# NodeLORA.net
KiCad netlist of a schematic drawn in Altium Designer
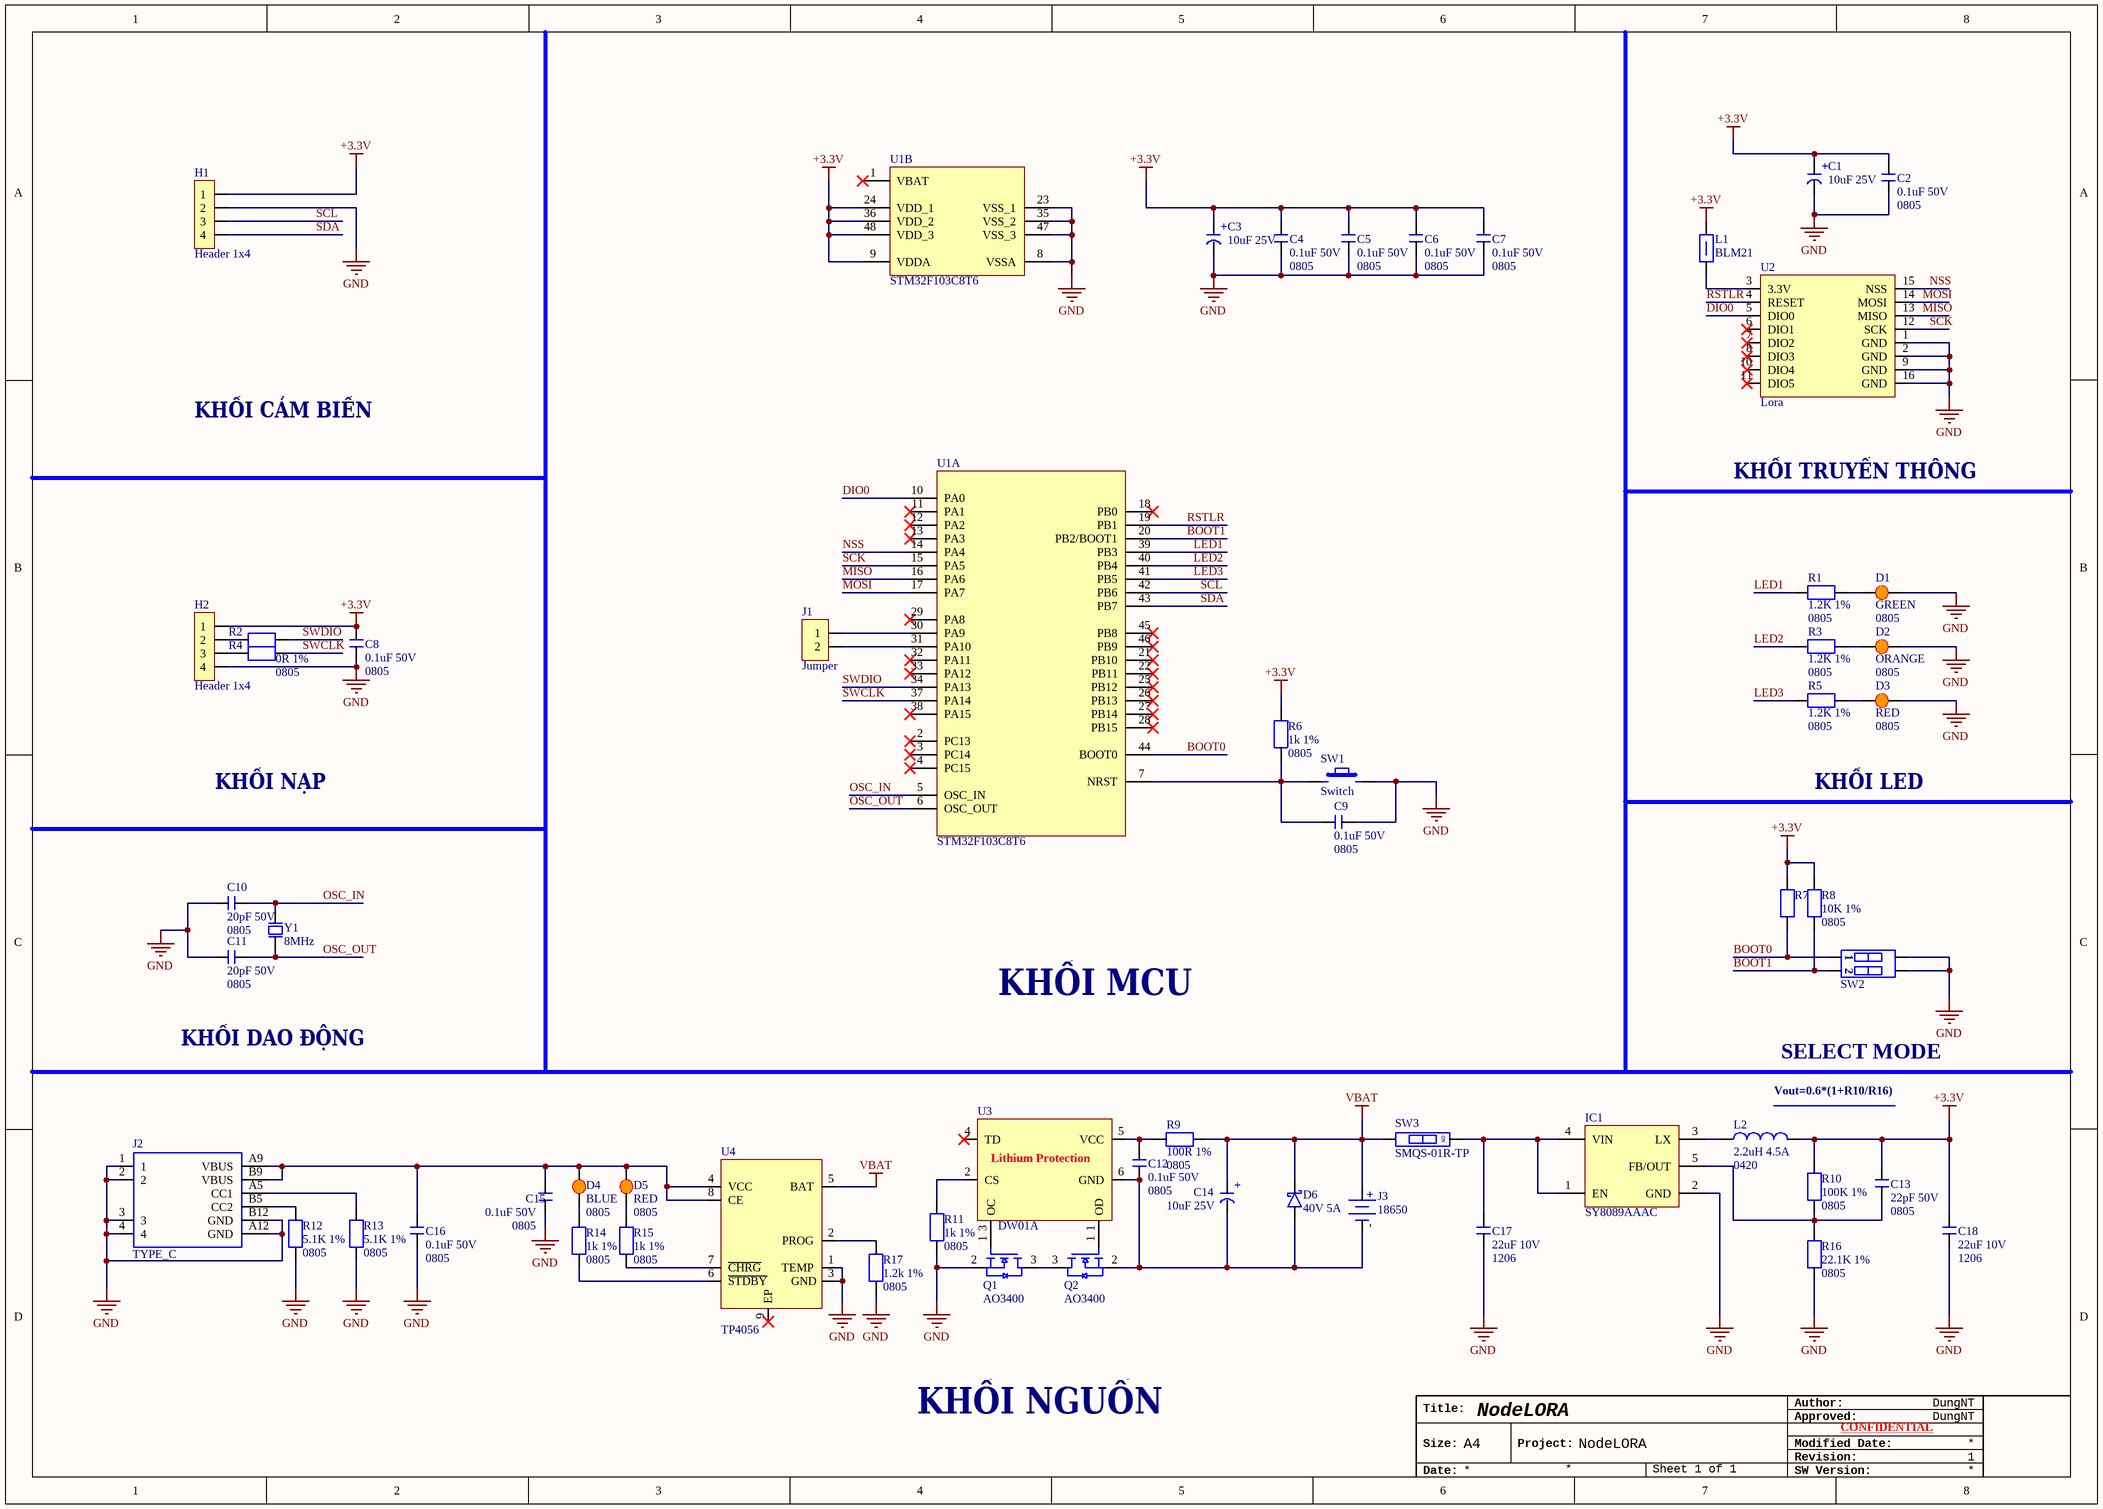
[diagram p0: NodeLORA.SchDoc]

(export (version "E")
  (design (tool "Eeschema 10.0.6"))
  (components
    (comp (ref "C1")
      (value "10uF 25V")
      (footprint "CAP-ALU-B")
      (description "10uF 25V 15mA@120Hz ±20% SMD,D4xL5.4mm Aluminum Electrolytic Capacitors - SMD ROHS")
      (fields (field (name "MANUFACTURER") "DMBJ"))
      (libsource (lib "Capacitor") (part "CAP_ALU_B_10uF_25V"))
    )
    (comp (ref "C2")
      (value "0.1uF 50V")
      (footprint "C0805")
      (description "0.1 µF ±10% 50V Ceramic Capacitor X7R 0805 (2012 Metric)")
      (fields (field (name "MANUFACTURER") "YAGEO") (field (name "PACKAGE") "0805"))
      (libsource (lib "Capacitor") (part "C0805_0.1uF_50V_10%"))
    )
    (comp (ref "C3")
      (value "10uF 25V")
      (footprint "CAP-ALU-B")
      (description "10uF 25V 15mA@120Hz ±20% SMD,D4xL5.4mm Aluminum Electrolytic Capacitors - SMD ROHS")
      (fields (field (name "MANUFACTURER") "DMBJ"))
      (libsource (lib "Capacitor") (part "CAP_ALU_B_10uF_25V"))
    )
    (comp (ref "C4")
      (value "0.1uF 50V")
      (footprint "C0805")
      (description "0.1 µF ±10% 50V Ceramic Capacitor X7R 0805 (2012 Metric)")
      (fields (field (name "MANUFACTURER") "YAGEO") (field (name "PACKAGE") "0805"))
      (libsource (lib "Capacitor") (part "C0805_0.1uF_50V_10%"))
    )
    (comp (ref "C5")
      (value "0.1uF 50V")
      (footprint "C0805")
      (description "0.1 µF ±10% 50V Ceramic Capacitor X7R 0805 (2012 Metric)")
      (fields (field (name "MANUFACTURER") "YAGEO") (field (name "PACKAGE") "0805"))
      (libsource (lib "Capacitor") (part "C0805_0.1uF_50V_10%"))
    )
    (comp (ref "C6")
      (value "0.1uF 50V")
      (footprint "C0805")
      (description "0.1 µF ±10% 50V Ceramic Capacitor X7R 0805 (2012 Metric)")
      (fields (field (name "MANUFACTURER") "YAGEO") (field (name "PACKAGE") "0805"))
      (libsource (lib "Capacitor") (part "C0805_0.1uF_50V_10%"))
    )
    (comp (ref "C7")
      (value "0.1uF 50V")
      (footprint "C0805")
      (description "0.1 µF ±10% 50V Ceramic Capacitor X7R 0805 (2012 Metric)")
      (fields (field (name "MANUFACTURER") "YAGEO") (field (name "PACKAGE") "0805"))
      (libsource (lib "Capacitor") (part "C0805_0.1uF_50V_10%"))
    )
    (comp (ref "C8")
      (value "0.1uF 50V")
      (footprint "C0805")
      (description "0.1 µF ±10% 50V Ceramic Capacitor X7R 0805 (2012 Metric)")
      (fields (field (name "MANUFACTURER") "YAGEO") (field (name "PACKAGE") "0805"))
      (libsource (lib "Capacitor") (part "C0805_0.1uF_50V_10%"))
    )
    (comp (ref "C9")
      (value "0.1uF 50V")
      (footprint "C0805")
      (description "0.1 µF ±10% 50V Ceramic Capacitor X7R 0805 (2012 Metric)")
      (fields (field (name "MANUFACTURER") "YAGEO") (field (name "PACKAGE") "0805"))
      (libsource (lib "Capacitor") (part "C0805_0.1uF_50V_10%"))
    )
    (comp (ref "C10")
      (value "20pF 50V")
      (footprint "C0805")
      (description "20 pF ±10% 50V Ceramic Capacitor X7R 0805 (2012 Metric)")
      (fields (field (name "MANUFACTURER") "KEMET") (field (name "PACKAGE") "0805"))
      (libsource (lib "Capacitor") (part "C0805_20pF_50V_10%"))
    )
    (comp (ref "C11")
      (value "20pF 50V")
      (footprint "C0805")
      (description "20 pF ±10% 50V Ceramic Capacitor X7R 0805 (2012 Metric)")
      (fields (field (name "MANUFACTURER") "KEMET") (field (name "PACKAGE") "0805"))
      (libsource (lib "Capacitor") (part "C0805_20pF_50V_10%"))
    )
    (comp (ref "C12")
      (value "0.1uF 50V")
      (footprint "C0805")
      (description "0.1 µF ±10% 50V Ceramic Capacitor X7R 0805 (2012 Metric)")
      (fields (field (name "MANUFACTURER") "YAGEO") (field (name "PACKAGE") "0805"))
      (libsource (lib "Capacitor") (part "C0805_0.1uF_50V_10%"))
    )
    (comp (ref "C13")
      (value "22pF 50V")
      (footprint "C0805")
      (description "22 pF ±10% 50V Ceramic Capacitor C0G, NP0 0805 (2012 Metric)")
      (fields (field (name "MANUFACTURER") "KEMET") (field (name "PACKAGE") "0805"))
      (libsource (lib "Capacitor") (part "C0805_22pF_50V_10%"))
    )
    (comp (ref "C14")
      (value "10uF 25V")
      (footprint "CAP-ALU-B")
      (description "10uF 25V 15mA@120Hz ±20% SMD,D4xL5.4mm Aluminum Electrolytic Capacitors - SMD ROHS")
      (fields (field (name "MANUFACTURER") "DMBJ"))
      (libsource (lib "Capacitor") (part "CAP_ALU_B_10uF_25V"))
    )
    (comp (ref "C15")
      (value "0.1uF 50V")
      (footprint "C0805")
      (description "0.1 µF ±10% 50V Ceramic Capacitor X7R 0805 (2012 Metric)")
      (fields (field (name "MANUFACTURER") "YAGEO") (field (name "PACKAGE") "0805"))
      (libsource (lib "Capacitor") (part "C0805_0.1uF_50V_10%"))
    )
    (comp (ref "C16")
      (value "0.1uF 50V")
      (footprint "C0805")
      (description "0.1 µF ±10% 50V Ceramic Capacitor X7R 0805 (2012 Metric)")
      (fields (field (name "MANUFACTURER") "YAGEO") (field (name "PACKAGE") "0805"))
      (libsource (lib "Capacitor") (part "C0805_0.1uF_50V_10%"))
    )
    (comp (ref "C17")
      (value "22uF 10V")
      (footprint "C1206")
      (description "22 µF ±20% 10V Ceramic Capacitor X7R 1206 (3216 Metric)")
      (fields (field (name "MANUFACTURER") "Samsung Electro-Mechanics") (field (name "PACKAGE") "1206"))
      (libsource (lib "Capacitor") (part "C1206_22uF_10V_10%"))
    )
    (comp (ref "C18")
      (value "22uF 10V")
      (footprint "C1206")
      (description "22 µF ±20% 10V Ceramic Capacitor X7R 1206 (3216 Metric)")
      (fields (field (name "MANUFACTURER") "Samsung Electro-Mechanics") (field (name "PACKAGE") "1206"))
      (libsource (lib "Capacitor") (part "C1206_22uF_10V_10%"))
    )
    (comp (ref "D1")
      (value "GREEN")
      (footprint "L0805-GREEN")
      (description "Green 570nm LED Indication - Discrete 2.1V 0805 (2012 Metric)")
      (fields (field (name "MANUFACTURER") "Kingbright") (field (name "PACKAGE") "0805"))
      (libsource (lib "Diode") (part "LED_0805_GREEN"))
    )
    (comp (ref "D2")
      (value "ORANGE")
      (footprint "L0805-ORANGE")
      (description "Orange 601nm LED Indication - Discrete 2.1V 0805 (2012 Metric)")
      (fields (field (name "MANUFACTURER") "Kingbright") (field (name "PACKAGE") "0805"))
      (libsource (lib "Diode") (part "LED_0805_ORANGE"))
    )
    (comp (ref "D3")
      (value "RED")
      (footprint "L0805-RED")
      (description "20mA 350mcd Colorless transparent lens 625nm Red 120° 2.2V 0805 LED Indication - Discrete ROHS")
      (fields (field (name "MANUFACTURER") "Kingbright") (field (name "PACKAGE") "0805"))
      (libsource (lib "Diode") (part "LED_0805_RED"))
    )
    (comp (ref "D4")
      (value "BLUE")
      (footprint "L0805-BLUE")
      (description "Blue 470nm LED Indication - Discrete 3.3V 0805 (2012 Metric)")
      (fields (field (name "MANUFACTURER") "LiteOnInc") (field (name "PACKAGE") "0805"))
      (libsource (lib "Diode") (part "LED_0805_BLUE"))
    )
    (comp (ref "D5")
      (value "RED")
      (footprint "L0805-RED")
      (description "20mA 350mcd Colorless transparent lens 625nm Red 120° 2.2V 0805 LED Indication - Discrete ROHS")
      (fields (field (name "MANUFACTURER") "Kingbright") (field (name "PACKAGE") "0805"))
      (libsource (lib "Diode") (part "LED_0805_RED"))
    )
    (comp (ref "D6")
      (value "40V 5A")
      (footprint "SMA(DO-214AC)")
      (description "40V Independent Type 550mV@5.0A 5A SMA(DO-214AC) Schottky Diodes ROHS")
      (fields (field (name "MANUFACTURER") "hongjiacheng"))
      (libsource (lib "Diode") (part "Diode_40V_5V_SMA"))
    )
    (comp (ref "H1")
      (value "Header 1x4")
      (footprint "H1x4M")
      (description "Connector Header 4 position")
      (fields (field (name "MANUFACTURER") "Adam Tech"))
      (libsource (lib "Connectors") (part "Header 1x4 2.54mm"))
    )
    (comp (ref "H2")
      (value "Header 1x4")
      (footprint "H1x4M")
      (description "Connector Header 4 position")
      (fields (field (name "MANUFACTURER") "Adam Tech"))
      (libsource (lib "Connectors") (part "Header 1x4 2.54mm"))
    )
    (comp (ref "IC1")
      (value "SY8089AAAC")
      (footprint "SOT-23-5")
      (description "Step-down type 2A 2.7V~5.5V SOT-23-5 DC-DC Converters ROHS")
      (fields (field (name "MANUFACTURER") "MaxLinear, Inc."))
      (libsource (lib "IC") (part "SY8089AAAC"))
    )
    (comp (ref "J1")
      (value "Jumper")
      (footprint "JUMPER2x")
      (description "40 Position Receptacle Connector 0.100\" (2.54mm) Through Hole")
      (fields (field (name "MANUFACTURER") "Marutsuelec"))
      (libsource (lib "Connectors") (part "Jumper 2P"))
    )
    (comp (ref "J2")
      (value "TYPE_C")
      (footprint "TYPE C 6P")
      (fields (field (name "MANUFACTURER") "Hanbo Electronic"))
      (libsource (lib "Connectors") (part "Type C 6P"))
    )
    (comp (ref "J3")
      (value "18650")
      (footprint "18650-PLUGIN")
      (description "Battery box 18650 SMD Button And Strip Battery Connector ROHS")
      (fields (field (name "MANUFACTURER") "MYOUNG"))
      (libsource (lib "Power") (part "Lithium 18650"))
    )
    (comp (ref "L1")
      (value "BLM21")
      (footprint "L0805")
      (description "120 Ohms @ 100 MHz 1 Power Line Ferrite Bead 0805 (2012 Metric) 1.55A 30mOhm")
      (fields (field (name "MANUFACTURER") "Murata Electronics"))
      (libsource (lib "Inductor") (part "BLM21PG121BH1D"))
    )
    (comp (ref "L2")
      (value "2.2uH 4.5A")
      (footprint "L0420")
      (description "4.5A 2.2uH Integrated molded inductor ±20% 5A SMD,0420 Power Inductors ROHS")
      (fields (field (name "MANUFACTURER") "TECHFUSE") (field (name "PACKAGE") "0420"))
      (libsource (lib "NodeLORA") (part "L0420_2.2uH_4.5A"))
    )
    (comp (ref "Q1")
      (value "AO3400")
      (footprint "SOT-23")
      (description "30V 5.8A 21mΩ@10V,5.8A 1.4W 1V@250uA 1 N-Channel SOT-23 MOSFETs ROHS")
      (fields (field (name "MANUFACTURER") "ElecSuper"))
      (libsource (lib "Trans_Mosfet") (part "AO3400"))
    )
    (comp (ref "Q2")
      (value "AO3400")
      (footprint "SOT-23")
      (description "30V 5.8A 21mΩ@10V,5.8A 1.4W 1V@250uA 1 N-Channel SOT-23 MOSFETs ROHS")
      (fields (field (name "MANUFACTURER") "ElecSuper"))
      (libsource (lib "Trans_Mosfet") (part "AO3400"))
    )
    (comp (ref "R1")
      (value "1.2K 1%")
      (footprint "R0805")
      (description "1.5 kOhms ±1% 0.125W, 1/8W Chip Resistor 0805 (2012 Metric) Automotive AEC-Q200 Thick Film")
      (fields (field (name "MANUFACTURER") "Stackpole Electronics Inc") (field (name "PACKAGE") "0805"))
      (libsource (lib "Resistor") (part "R0805_1.5K"))
    )
    (comp (ref "R2")
      (value "0R 1%")
      (footprint "R0805")
      (description "0 Ohms ±1% 0.125W, 1/8W Chip Resistor 0805 (2012 Metric) Anti-Sulfur Thick Film")
      (fields (field (name "MANUFACTURER") "Thin Film Technology Corp."))
      (libsource (lib "Resistor") (part "R0805_0R"))
    )
    (comp (ref "R3")
      (value "1.2K 1%")
      (footprint "R0805")
      (description "1.5 kOhms ±1% 0.125W, 1/8W Chip Resistor 0805 (2012 Metric) Automotive AEC-Q200 Thick Film")
      (fields (field (name "MANUFACTURER") "Stackpole Electronics Inc") (field (name "PACKAGE") "0805"))
      (libsource (lib "Resistor") (part "R0805_1.5K"))
    )
    (comp (ref "R4")
      (value "0R 1%")
      (footprint "R0805")
      (description "0 Ohms ±1% 0.125W, 1/8W Chip Resistor 0805 (2012 Metric) Anti-Sulfur Thick Film")
      (fields (field (name "MANUFACTURER") "Thin Film Technology Corp.") (field (name "PACKAGE") "0805"))
      (libsource (lib "Resistor") (part "R0805_0R"))
    )
    (comp (ref "R5")
      (value "1.2K 1%")
      (footprint "R0805")
      (description "1.5 kOhms ±1% 0.125W, 1/8W Chip Resistor 0805 (2012 Metric) Automotive AEC-Q200 Thick Film")
      (fields (field (name "MANUFACTURER") "Stackpole Electronics Inc") (field (name "PACKAGE") "0805"))
      (libsource (lib "Resistor") (part "R0805_1.5K"))
    )
    (comp (ref "R6")
      (value "1k 1%")
      (footprint "R0805")
      (description "1 kOhms ±1% 0.125W, 1/8W Chip Resistor 0805 (2012 Metric) Automotive AEC-Q200 Thick Film")
      (fields (field (name "MANUFACTURER") "Stackpole Electronics Inc") (field (name "PACKAGE") "0805"))
      (libsource (lib "Resistor") (part "R0805_1K"))
    )
    (comp (ref "R7")
      (value "10K 1%")
      (footprint "R0805")
      (description "10 kOhms ±1% 0.125W, 1/8W Chip Resistor 0805 (2012 Metric) Automotive AEC-Q200 Thick Film")
      (fields (field (name "MANUFACTURER") "Stackpole Electronics Inc"))
      (libsource (lib "Resistor") (part "R0805_10K"))
    )
    (comp (ref "R8")
      (value "10K 1%")
      (footprint "R0805")
      (description "10 kOhms ±1% 0.125W, 1/8W Chip Resistor 0805 (2012 Metric) Automotive AEC-Q200 Thick Film")
      (fields (field (name "MANUFACTURER") "Stackpole Electronics Inc") (field (name "PACKAGE") "0805"))
      (libsource (lib "Resistor") (part "R0805_10K"))
    )
    (comp (ref "R9")
      (value "100R 1%")
      (footprint "R0805")
      (description "100 Ohms ±1% 0.125W, 1/8W Chip Resistor 0805 (2012 Metric) Automotive AEC-Q200 Thick Film")
      (fields (field (name "MANUFACTURER") "Stackpole Electronics Inc") (field (name "PACKAGE") "0805"))
      (libsource (lib "Resistor") (part "R0805_100R"))
    )
    (comp (ref "R10")
      (value "100K 1%")
      (footprint "R0805")
      (description "100 kOhms ±1% 0.125W, 1/8W Chip Resistor 0805 (2012 Metric) Automotive AEC-Q200 Thick Film")
      (fields (field (name "MANUFACTURER") "Stackpole Electronics Inc") (field (name "PACKAGE") "0805"))
      (libsource (lib "Resistor") (part "R0805_100K"))
    )
    (comp (ref "R11")
      (value "1k 1%")
      (footprint "R0805")
      (description "1 kOhms ±1% 0.125W, 1/8W Chip Resistor 0805 (2012 Metric) Automotive AEC-Q200 Thick Film")
      (fields (field (name "MANUFACTURER") "Stackpole Electronics Inc") (field (name "PACKAGE") "0805"))
      (libsource (lib "Resistor") (part "R0805_1K"))
    )
    (comp (ref "R12")
      (value "5.1K 1%")
      (footprint "R0805")
      (description "5.1 kOhms ±1% 0.125W, 1/8W Chip Resistor 0805 (2012 Metric) Automotive AEC-Q200 Thick Film")
      (fields (field (name "MANUFACTURER") "Stackpole Electronics Inc") (field (name "PACKAGE") "0805"))
      (libsource (lib "Resistor") (part "R0805_5.1K"))
    )
    (comp (ref "R13")
      (value "5.1K 1%")
      (footprint "R0805")
      (description "5.1 kOhms ±1% 0.125W, 1/8W Chip Resistor 0805 (2012 Metric) Automotive AEC-Q200 Thick Film")
      (fields (field (name "MANUFACTURER") "Stackpole Electronics Inc") (field (name "PACKAGE") "0805"))
      (libsource (lib "Resistor") (part "R0805_5.1K"))
    )
    (comp (ref "R14")
      (value "1k 1%")
      (footprint "R0805")
      (description "1 kOhms ±1% 0.125W, 1/8W Chip Resistor 0805 (2012 Metric) Automotive AEC-Q200 Thick Film")
      (fields (field (name "MANUFACTURER") "Stackpole Electronics Inc") (field (name "PACKAGE") "0805"))
      (libsource (lib "Resistor") (part "R0805_1K"))
    )
    (comp (ref "R15")
      (value "1k 1%")
      (footprint "R0805")
      (description "1 kOhms ±1% 0.125W, 1/8W Chip Resistor 0805 (2012 Metric) Automotive AEC-Q200 Thick Film")
      (fields (field (name "MANUFACTURER") "Stackpole Electronics Inc") (field (name "PACKAGE") "0805"))
      (libsource (lib "Resistor") (part "R0805_1K"))
    )
    (comp (ref "R16")
      (value "22.1K 1%")
      (footprint "R0805")
      (description "22.1 kOhms ±1% 0.125W, 1/8W Chip Resistor 0805 (2012 Metric) Automotive AEC-Q200 Thick Film")
      (fields (field (name "MANUFACTURER") "Stackpole Electronics Inc") (field (name "PACKAGE") "0805"))
      (libsource (lib "Resistor") (part "R0805_22.1K"))
    )
    (comp (ref "R17")
      (value "1.2k 1%")
      (footprint "R0805")
      (description "1.2 kOhms ±1% 0.125W, 1/8W Chip Resistor 0805 (2012 Metric) Automotive AEC-Q200 Thick Film")
      (fields (field (name "MANUFACTURER") "Stackpole Electronics Inc") (field (name "PACKAGE") "0805"))
      (libsource (lib "Resistor") (part "R0805_1.2K"))
    )
    (comp (ref "SW1")
      (value "Switch")
      (footprint "SW_6X3.5mm_2SMD")
      (description "Tactile Switch SPST-NO Top Actuated Surface Mount")
      (fields (field (name "MANUFACTURER") "Omron Electronics Inc-EMC Div"))
      (libsource (lib "Connectors") (part "Switch_2SMD"))
    )
    (comp (ref "SW2")
      (value "VDG-02HG-R")
      (footprint "DIPSWITCHES_2P")
      (description "1 Digit 24V 25mA Red 5 Thousand Times Flat Toggle, Raised Style DIP Switches ROHS")
      (fields (field (name "MANUFACTURER") "Cixi Tonver Elec"))
      (libsource (lib "Connectors") (part "BitSwitch_2P"))
    )
    (comp (ref "SW3")
      (value "SMQS-01R-TP")
      (footprint "SMSWITCH_1P")
      (description "1 Digit 24V 25mA Red 5 Thousand Times Flat Toggle, Raised Style DIP Switches ROHS")
      (fields (field (name "MANUFACTURER") "SM Switch"))
      (libsource (lib "Connectors") (part "BitSwitch_1P"))
    )
    (comp (ref "U1")
      (value "STM32F103C8T6")
      (footprint "LQFP-48")
      (description "ARM® Cortex®-M3 STM32F1 Microcontroller IC 32-Bit Single-Core 72MHz 64KB (64K x 8) FLASH")
      (fields (field (name "MANUFACTURER") "STMicroelectronics"))
      (libsource (lib "MCU") (part "STM32F103C8T6"))
    )
    (comp (ref "U2")
      (value "Lora")
      (footprint "RA-02-SX1278")
      (description "-140dBm 20dBm SPI SMD-16P LoRa Modules ROHS")
      (fields (field (name "MANUFACTURER") "Ai-Thinker"))
      (libsource (lib "NodeLORA") (part "Ra-02"))
    )
    (comp (ref "U3")
      (value "DW01A")
      (footprint "SOT-23-6")
      (description "-300mV~8V Lithium-ion/Polymer 1 SOT-23-6 Battery Management ROHS")
      (fields (field (name "MANUFACTURER") "YONGYUTAI"))
      (libsource (lib "IC") (part "DW01A"))
    )
    (comp (ref "U4")
      (value "TP4056")
      (footprint "ESOP-8")
      (description "ESOP-8 Battery Management ROHS")
      (fields (field (name "MANUFACTURER") "TOPPOWER(Nanjing Extension Microelectronics)"))
      (libsource (lib "IC") (part "TP4056"))
    )
    (comp (ref "Y1")
      (value "8MHz")
      (footprint "5032-2")
      (description "8MHz Surface Mount Crystal 18pF ±30ppm SMD5032 Crystals ROHS")
      (fields (field (name "MANUFACTURER") "TXC Corp"))
      (libsource (lib "Crystal") (part "5032_8MHz"))
    )
  )
  (nets
    (net (code "1") (name "+3.3V") (class "Default")
      (node (ref "C1") (pin "1") (pinfunction "1_1") (pintype "passive"))
      (node (ref "C13") (pin "2") (pinfunction "2_2") (pintype "passive"))
      (node (ref "C18") (pin "2") (pinfunction "2_2") (pintype "passive"))
      (node (ref "C2") (pin "2") (pinfunction "2_2") (pintype "passive"))
      (node (ref "C3") (pin "1") (pinfunction "1_1") (pintype "passive"))
      (node (ref "C4") (pin "2") (pinfunction "2_2") (pintype "passive"))
      (node (ref "C5") (pin "2") (pinfunction "2_2") (pintype "passive"))
      (node (ref "C6") (pin "2") (pinfunction "2_2") (pintype "passive"))
      (node (ref "C7") (pin "2") (pinfunction "2_2") (pintype "passive"))
      (node (ref "C8") (pin "2") (pinfunction "2_2") (pintype "passive"))
      (node (ref "H1") (pin "1") (pinfunction "1_1") (pintype "passive"))
      (node (ref "H2") (pin "1") (pinfunction "1_1") (pintype "passive"))
      (node (ref "L1") (pin "2") (pinfunction "2_2") (pintype "passive"))
      (node (ref "L2") (pin "2") (pinfunction "2_2") (pintype "passive"))
      (node (ref "R10") (pin "2") (pinfunction "2_2") (pintype "passive"))
      (node (ref "R6") (pin "1") (pinfunction "1_1") (pintype "passive"))
      (node (ref "R7") (pin "2") (pinfunction "2_2") (pintype "passive"))
      (node (ref "R8") (pin "2") (pinfunction "2_2") (pintype "passive"))
      (node (ref "U1") (pin "24") (pinfunction "VDD_1_24") (pintype "passive"))
      (node (ref "U1") (pin "36") (pinfunction "VDD_2_36") (pintype "passive"))
      (node (ref "U1") (pin "48") (pinfunction "VDD_3_48") (pintype "passive"))
      (node (ref "U1") (pin "9") (pinfunction "VDDA_9") (pintype "passive"))
    )
    (net (code "2") (name "/BOOT0") (class "Default")
      (node (ref "R7") (pin "1") (pinfunction "1_1") (pintype "passive"))
      (node (ref "SW2") (pin "1") (pinfunction "1_1") (pintype "passive"))
      (node (ref "U1") (pin "44") (pinfunction "BOOT0_44") (pintype "passive"))
    )
    (net (code "3") (name "/BOOT1") (class "Default")
      (node (ref "R8") (pin "1") (pinfunction "1_1") (pintype "passive"))
      (node (ref "SW2") (pin "2") (pinfunction "2_2") (pintype "passive"))
      (node (ref "U1") (pin "20") (pinfunction "PB2/BOOT1_20") (pintype "passive"))
    )
    (net (code "4") (name "/DIO0") (class "Default")
      (node (ref "U1") (pin "10") (pinfunction "PA0_10") (pintype "passive"))
      (node (ref "U2") (pin "5") (pinfunction "DIO0_5") (pintype "passive"))
    )
    (net (code "5") (name "/LED1") (class "Default")
      (node (ref "R1") (pin "1") (pinfunction "1_1") (pintype "passive"))
      (node (ref "U1") (pin "39") (pinfunction "PB3_39") (pintype "passive"))
    )
    (net (code "6") (name "/LED2") (class "Default")
      (node (ref "R3") (pin "1") (pinfunction "1_1") (pintype "passive"))
      (node (ref "U1") (pin "40") (pinfunction "PB4_40") (pintype "passive"))
    )
    (net (code "7") (name "/LED3") (class "Default")
      (node (ref "R5") (pin "1") (pinfunction "1_1") (pintype "passive"))
      (node (ref "U1") (pin "41") (pinfunction "PB5_41") (pintype "passive"))
    )
    (net (code "8") (name "/MISO") (class "Default")
      (node (ref "U1") (pin "16") (pinfunction "PA6_16") (pintype "passive"))
      (node (ref "U2") (pin "13") (pinfunction "MISO_13") (pintype "passive"))
    )
    (net (code "9") (name "/MOSI") (class "Default")
      (node (ref "U1") (pin "17") (pinfunction "PA7_17") (pintype "passive"))
      (node (ref "U2") (pin "14") (pinfunction "MOSI_14") (pintype "passive"))
    )
    (net (code "10") (name "/NSS") (class "Default")
      (node (ref "U1") (pin "14") (pinfunction "PA4_14") (pintype "passive"))
      (node (ref "U2") (pin "15") (pinfunction "NSS_15") (pintype "passive"))
    )
    (net (code "11") (name "/OSC_IN") (class "Default")
      (node (ref "C10") (pin "2") (pinfunction "2_2") (pintype "passive"))
      (node (ref "U1") (pin "5") (pinfunction "OSC_IN_5") (pintype "passive"))
      (node (ref "Y1") (pin "2") (pinfunction "2_2") (pintype "passive"))
    )
    (net (code "12") (name "/OSC_OUT") (class "Default")
      (node (ref "C11") (pin "2") (pinfunction "2_2") (pintype "passive"))
      (node (ref "U1") (pin "6") (pinfunction "OSC_OUT_6") (pintype "passive"))
      (node (ref "Y1") (pin "1") (pinfunction "1_1") (pintype "passive"))
    )
    (net (code "13") (name "/RSTLR") (class "Default")
      (node (ref "U1") (pin "19") (pinfunction "PB1_19") (pintype "passive"))
      (node (ref "U2") (pin "4") (pinfunction "RESET_4") (pintype "passive"))
    )
    (net (code "14") (name "/SCK") (class "Default")
      (node (ref "U1") (pin "15") (pinfunction "PA5_15") (pintype "passive"))
      (node (ref "U2") (pin "12") (pinfunction "SCK_12") (pintype "passive"))
    )
    (net (code "15") (name "/SCL") (class "Default")
      (node (ref "H1") (pin "3") (pinfunction "3_3") (pintype "passive"))
      (node (ref "U1") (pin "42") (pinfunction "PB6_42") (pintype "passive"))
    )
    (net (code "16") (name "/SDA") (class "Default")
      (node (ref "H1") (pin "4") (pinfunction "4_4") (pintype "passive"))
      (node (ref "U1") (pin "43") (pinfunction "PB7_43") (pintype "passive"))
    )
    (net (code "17") (name "/SWCLK") (class "Default")
      (node (ref "R4") (pin "2") (pinfunction "2_2") (pintype "passive"))
      (node (ref "U1") (pin "37") (pinfunction "PA14_37") (pintype "passive"))
    )
    (net (code "18") (name "/SWDIO") (class "Default")
      (node (ref "R2") (pin "2") (pinfunction "2_2") (pintype "passive"))
      (node (ref "U1") (pin "34") (pinfunction "PA13_34") (pintype "passive"))
    )
    (net (code "19") (name "GND") (class "Default")
      (node (ref "C1") (pin "2") (pinfunction "2_2") (pintype "passive"))
      (node (ref "C10") (pin "1") (pinfunction "1_1") (pintype "passive"))
      (node (ref "C11") (pin "1") (pinfunction "1_1") (pintype "passive"))
      (node (ref "C15") (pin "1") (pinfunction "1_1") (pintype "passive"))
      (node (ref "C16") (pin "1") (pinfunction "1_1") (pintype "passive"))
      (node (ref "C17") (pin "1") (pinfunction "1_1") (pintype "passive"))
      (node (ref "C18") (pin "1") (pinfunction "1_1") (pintype "passive"))
      (node (ref "C2") (pin "1") (pinfunction "1_1") (pintype "passive"))
      (node (ref "C3") (pin "2") (pinfunction "2_2") (pintype "passive"))
      (node (ref "C4") (pin "1") (pinfunction "1_1") (pintype "passive"))
      (node (ref "C5") (pin "1") (pinfunction "1_1") (pintype "passive"))
      (node (ref "C6") (pin "1") (pinfunction "1_1") (pintype "passive"))
      (node (ref "C7") (pin "1") (pinfunction "1_1") (pintype "passive"))
      (node (ref "C8") (pin "1") (pinfunction "1_1") (pintype "passive"))
      (node (ref "C9") (pin "1") (pinfunction "1_1") (pintype "passive"))
      (node (ref "D1") (pin "2") (pinfunction "2_2") (pintype "passive"))
      (node (ref "D2") (pin "2") (pinfunction "2_2") (pintype "passive"))
      (node (ref "D3") (pin "2") (pinfunction "2_2") (pintype "passive"))
      (node (ref "H1") (pin "2") (pinfunction "2_2") (pintype "passive"))
      (node (ref "H2") (pin "4") (pinfunction "4_4") (pintype "passive"))
      (node (ref "IC1") (pin "2") (pinfunction "GND_2") (pintype "passive"))
      (node (ref "J2") (pin "1") (pinfunction "1_1") (pintype "passive"))
      (node (ref "J2") (pin "2") (pinfunction "2_2") (pintype "passive"))
      (node (ref "J2") (pin "3") (pinfunction "3_3") (pintype "passive"))
      (node (ref "J2") (pin "4") (pinfunction "4_4") (pintype "passive"))
      (node (ref "J2") (pin "A12") (pinfunction "GND_A12") (pintype "passive"))
      (node (ref "J2") (pin "B12") (pinfunction "GND_B12") (pintype "passive"))
      (node (ref "Q1") (pin "2") (pinfunction "Source_2") (pintype "passive"))
      (node (ref "R11") (pin "2") (pinfunction "2_2") (pintype "passive"))
      (node (ref "R12") (pin "1") (pinfunction "1_1") (pintype "passive"))
      (node (ref "R13") (pin "1") (pinfunction "1_1") (pintype "passive"))
      (node (ref "R16") (pin "1") (pinfunction "1_1") (pintype "passive"))
      (node (ref "R17") (pin "1") (pinfunction "1_1") (pintype "passive"))
      (node (ref "SW1") (pin "2") (pinfunction "2_2") (pintype "passive"))
      (node (ref "SW2") (pin "3") (pinfunction "3_3") (pintype "passive"))
      (node (ref "SW2") (pin "4") (pinfunction "4_4") (pintype "passive"))
      (node (ref "U1") (pin "23") (pinfunction "VSS_1_23") (pintype "passive"))
      (node (ref "U1") (pin "35") (pinfunction "VSS_2_35") (pintype "passive"))
      (node (ref "U1") (pin "47") (pinfunction "VSS_3_47") (pintype "passive"))
      (node (ref "U1") (pin "8") (pinfunction "VSSA_8") (pintype "passive"))
      (node (ref "U2") (pin "1") (pinfunction "GND_1") (pintype "passive"))
      (node (ref "U2") (pin "16") (pinfunction "GND_16") (pintype "passive"))
      (node (ref "U2") (pin "2") (pinfunction "GND_2") (pintype "passive"))
      (node (ref "U2") (pin "9") (pinfunction "GND_9") (pintype "passive"))
      (node (ref "U4") (pin "1") (pinfunction "TEMP_1") (pintype "passive"))
      (node (ref "U4") (pin "3") (pinfunction "GND_3") (pintype "passive"))
    )
    (net (code "20") (name "Net-(D1-Pad1)") (class "Default")
      (node (ref "D1") (pin "1") (pinfunction "1_1") (pintype "passive"))
      (node (ref "R1") (pin "2") (pinfunction "2_2") (pintype "passive"))
    )
    (net (code "21") (name "Net-(D2-Pad1)") (class "Default")
      (node (ref "D2") (pin "1") (pinfunction "1_1") (pintype "passive"))
      (node (ref "R3") (pin "2") (pinfunction "2_2") (pintype "passive"))
    )
    (net (code "22") (name "Net-(D3-Pad1)") (class "Default")
      (node (ref "D3") (pin "1") (pinfunction "1_1") (pintype "passive"))
      (node (ref "R5") (pin "2") (pinfunction "2_2") (pintype "passive"))
    )
    (net (code "23") (name "Net-(D4-Pad2)") (class "Default")
      (node (ref "D4") (pin "2") (pinfunction "2_2") (pintype "passive"))
      (node (ref "R14") (pin "1") (pinfunction "1_1") (pintype "passive"))
    )
    (net (code "24") (name "Net-(D5-Pad2)") (class "Default")
      (node (ref "D5") (pin "2") (pinfunction "2_2") (pintype "passive"))
      (node (ref "R15") (pin "1") (pinfunction "1_1") (pintype "passive"))
    )
    (net (code "25") (name "Net-(H2-Pad2)") (class "Default")
      (node (ref "H2") (pin "2") (pinfunction "2_2") (pintype "passive"))
      (node (ref "R2") (pin "1") (pinfunction "1_1") (pintype "passive"))
    )
    (net (code "26") (name "Net-(H2-Pad3)") (class "Default")
      (node (ref "H2") (pin "3") (pinfunction "3_3") (pintype "passive"))
      (node (ref "R4") (pin "1") (pinfunction "1_1") (pintype "passive"))
    )
    (net (code "27") (name "Net-(IC1-EN)") (class "Default")
      (node (ref "C17") (pin "2") (pinfunction "2_2") (pintype "passive"))
      (node (ref "IC1") (pin "1") (pinfunction "EN_1") (pintype "passive"))
      (node (ref "IC1") (pin "4") (pinfunction "VIN_4") (pintype "passive"))
      (node (ref "SW3") (pin "2") (pinfunction "2_2") (pintype "passive"))
    )
    (net (code "28") (name "Net-(IC1-FB{slash}OUT)") (class "Default")
      (node (ref "C13") (pin "1") (pinfunction "1_1") (pintype "passive"))
      (node (ref "IC1") (pin "5") (pinfunction "FB/OUT_5") (pintype "passive"))
      (node (ref "R10") (pin "1") (pinfunction "1_1") (pintype "passive"))
      (node (ref "R16") (pin "2") (pinfunction "2_2") (pintype "passive"))
    )
    (net (code "29") (name "Net-(IC1-LX)") (class "Default")
      (node (ref "IC1") (pin "3") (pinfunction "LX_3") (pintype "passive"))
      (node (ref "L2") (pin "1") (pinfunction "1_1") (pintype "passive"))
    )
    (net (code "30") (name "Net-(J2-CC1)") (class "Default")
      (node (ref "J2") (pin "A5") (pinfunction "CC1_A5") (pintype "passive"))
      (node (ref "R13") (pin "2") (pinfunction "2_2") (pintype "passive"))
    )
    (net (code "31") (name "Net-(J2-CC2)") (class "Default")
      (node (ref "J2") (pin "B5") (pinfunction "CC2_B5") (pintype "passive"))
      (node (ref "R12") (pin "2") (pinfunction "2_2") (pintype "passive"))
    )
    (net (code "32") (name "Net-(Q1-Drain)") (class "Default")
      (node (ref "Q1") (pin "3") (pinfunction "Drain_3") (pintype "passive"))
      (node (ref "Q2") (pin "3") (pinfunction "Drain_3") (pintype "passive"))
    )
    (net (code "33") (name "Net-(Q1-Gate)") (class "Default")
      (node (ref "Q1") (pin "1") (pinfunction "Gate_1") (pintype "passive"))
      (node (ref "U3") (pin "3") (pinfunction "OC_3") (pintype "passive"))
    )
    (net (code "34") (name "Net-(Q2-Gate)") (class "Default")
      (node (ref "Q2") (pin "1") (pinfunction "Gate_1") (pintype "passive"))
      (node (ref "U3") (pin "1") (pinfunction "OD_1") (pintype "passive"))
    )
    (net (code "35") (name "Net-(Q2-Source)") (class "Default")
      (node (ref "C12") (pin "1") (pinfunction "1_1") (pintype "passive"))
      (node (ref "C14") (pin "2") (pinfunction "2_2") (pintype "passive"))
      (node (ref "D6") (pin "1") (pinfunction "1_1") (pintype "passive"))
      (node (ref "J3") (pin "2") (pinfunction "2_2") (pintype "passive"))
      (node (ref "Q2") (pin "2") (pinfunction "Source_2") (pintype "passive"))
      (node (ref "U3") (pin "6") (pinfunction "GND_6") (pintype "passive"))
    )
    (net (code "36") (name "Net-(U1A-NRST)") (class "Default")
      (node (ref "C9") (pin "2") (pinfunction "2_2") (pintype "passive"))
      (node (ref "R6") (pin "2") (pinfunction "2_2") (pintype "passive"))
      (node (ref "SW1") (pin "1") (pinfunction "1_1") (pintype "passive"))
      (node (ref "U1") (pin "7") (pinfunction "NRST_7") (pintype "passive"))
    )
    (net (code "37") (name "Net-(U1A-PA9)") (class "Default")
      (node (ref "J1") (pin "1") (pinfunction "1_1") (pintype "passive"))
      (node (ref "U1") (pin "30") (pinfunction "PA9_30") (pintype "passive"))
    )
    (net (code "38") (name "Net-(U1A-PA10)") (class "Default")
      (node (ref "J1") (pin "2") (pinfunction "2_2") (pintype "passive"))
      (node (ref "U1") (pin "31") (pinfunction "PA10_31") (pintype "passive"))
    )
    (net (code "39") (name "Net-(U2-3.3V)") (class "Default")
      (node (ref "L1") (pin "1") (pinfunction "1_1") (pintype "passive"))
      (node (ref "U2") (pin "3") (pinfunction "3.3V_3") (pintype "passive"))
    )
    (net (code "40") (name "Net-(U3-CS)") (class "Default")
      (node (ref "R11") (pin "1") (pinfunction "1_1") (pintype "passive"))
      (node (ref "U3") (pin "2") (pinfunction "CS_2") (pintype "passive"))
    )
    (net (code "41") (name "Net-(U3-VCC)") (class "Default")
      (node (ref "C12") (pin "2") (pinfunction "2_2") (pintype "passive"))
      (node (ref "R9") (pin "1") (pinfunction "1_1") (pintype "passive"))
      (node (ref "U3") (pin "5") (pinfunction "VCC_5") (pintype "passive"))
    )
    (net (code "42") (name "Net-(U4-CE)") (class "Default")
      (node (ref "C15") (pin "2") (pinfunction "2_2") (pintype "passive"))
      (node (ref "C16") (pin "2") (pinfunction "2_2") (pintype "passive"))
      (node (ref "D4") (pin "1") (pinfunction "1_1") (pintype "passive"))
      (node (ref "D5") (pin "1") (pinfunction "1_1") (pintype "passive"))
      (node (ref "J2") (pin "A9") (pinfunction "VBUS_A9") (pintype "passive"))
      (node (ref "J2") (pin "B9") (pinfunction "VBUS_B9") (pintype "passive"))
      (node (ref "U4") (pin "4") (pinfunction "VCC_4") (pintype "passive"))
      (node (ref "U4") (pin "8") (pinfunction "CE_8") (pintype "passive"))
    )
    (net (code "43") (name "Net-(U4-PROG)") (class "Default")
      (node (ref "R17") (pin "2") (pinfunction "2_2") (pintype "passive"))
      (node (ref "U4") (pin "2") (pinfunction "PROG_2") (pintype "passive"))
    )
    (net (code "44") (name "Net-(U4-~{CHRG})") (class "Default")
      (node (ref "R15") (pin "2") (pinfunction "2_2") (pintype "passive"))
      (node (ref "U4") (pin "7") (pinfunction "~{CHRG}_7") (pintype "passive"))
    )
    (net (code "45") (name "Net-(U4-~{STDBY})") (class "Default")
      (node (ref "R14") (pin "2") (pinfunction "2_2") (pintype "passive"))
      (node (ref "U4") (pin "6") (pinfunction "~{STDBY}_6") (pintype "passive"))
    )
    (net (code "46") (name "VBAT") (class "Default")
      (node (ref "C14") (pin "1") (pinfunction "1_1") (pintype "passive"))
      (node (ref "D6") (pin "2") (pinfunction "2_2") (pintype "passive"))
      (node (ref "J3") (pin "1") (pinfunction "1_1") (pintype "passive"))
      (node (ref "R9") (pin "2") (pinfunction "2_2") (pintype "passive"))
      (node (ref "SW3") (pin "1") (pinfunction "1_1") (pintype "passive"))
      (node (ref "U4") (pin "5") (pinfunction "BAT_5") (pintype "passive"))
    )
    (net (code "47") (name "unconnected-(U1A-PA1-Pad11)") (class "Default")
      (node (ref "U1") (pin "11") (pinfunction "PA1_11") (pintype "passive+no_connect"))
    )
    (net (code "48") (name "unconnected-(U1A-PA2-Pad12)") (class "Default")
      (node (ref "U1") (pin "12") (pinfunction "PA2_12") (pintype "passive+no_connect"))
    )
    (net (code "49") (name "unconnected-(U1A-PA3-Pad13)") (class "Default")
      (node (ref "U1") (pin "13") (pinfunction "PA3_13") (pintype "passive+no_connect"))
    )
    (net (code "50") (name "unconnected-(U1A-PA8-Pad29)") (class "Default")
      (node (ref "U1") (pin "29") (pinfunction "PA8_29") (pintype "passive+no_connect"))
    )
    (net (code "51") (name "unconnected-(U1A-PA11-Pad32)") (class "Default")
      (node (ref "U1") (pin "32") (pinfunction "PA11_32") (pintype "passive+no_connect"))
    )
    (net (code "52") (name "unconnected-(U1A-PA12-Pad33)") (class "Default")
      (node (ref "U1") (pin "33") (pinfunction "PA12_33") (pintype "passive+no_connect"))
    )
    (net (code "53") (name "unconnected-(U1A-PA15-Pad38)") (class "Default")
      (node (ref "U1") (pin "38") (pinfunction "PA15_38") (pintype "passive+no_connect"))
    )
    (net (code "54") (name "unconnected-(U1A-PB0-Pad18)") (class "Default")
      (node (ref "U1") (pin "18") (pinfunction "PB0_18") (pintype "passive+no_connect"))
    )
    (net (code "55") (name "unconnected-(U1A-PB8-Pad45)") (class "Default")
      (node (ref "U1") (pin "45") (pinfunction "PB8_45") (pintype "passive+no_connect"))
    )
    (net (code "56") (name "unconnected-(U1A-PB9-Pad46)") (class "Default")
      (node (ref "U1") (pin "46") (pinfunction "PB9_46") (pintype "passive+no_connect"))
    )
    (net (code "57") (name "unconnected-(U1A-PB10-Pad21)") (class "Default")
      (node (ref "U1") (pin "21") (pinfunction "PB10_21") (pintype "passive+no_connect"))
    )
    (net (code "58") (name "unconnected-(U1A-PB11-Pad22)") (class "Default")
      (node (ref "U1") (pin "22") (pinfunction "PB11_22") (pintype "passive+no_connect"))
    )
    (net (code "59") (name "unconnected-(U1A-PB12-Pad25)") (class "Default")
      (node (ref "U1") (pin "25") (pinfunction "PB12_25") (pintype "passive+no_connect"))
    )
    (net (code "60") (name "unconnected-(U1A-PB13-Pad26)") (class "Default")
      (node (ref "U1") (pin "26") (pinfunction "PB13_26") (pintype "passive+no_connect"))
    )
    (net (code "61") (name "unconnected-(U1A-PB14-Pad27)") (class "Default")
      (node (ref "U1") (pin "27") (pinfunction "PB14_27") (pintype "passive+no_connect"))
    )
    (net (code "62") (name "unconnected-(U1A-PB15-Pad28)") (class "Default")
      (node (ref "U1") (pin "28") (pinfunction "PB15_28") (pintype "passive+no_connect"))
    )
    (net (code "63") (name "unconnected-(U1A-PC13-Pad2)") (class "Default")
      (node (ref "U1") (pin "2") (pinfunction "PC13_2") (pintype "passive+no_connect"))
    )
    (net (code "64") (name "unconnected-(U1A-PC14-Pad3)") (class "Default")
      (node (ref "U1") (pin "3") (pinfunction "PC14_3") (pintype "passive+no_connect"))
    )
    (net (code "65") (name "unconnected-(U1A-PC15-Pad4)") (class "Default")
      (node (ref "U1") (pin "4") (pinfunction "PC15_4") (pintype "passive+no_connect"))
    )
    (net (code "66") (name "unconnected-(U1B-VBAT-Pad1)") (class "Default")
      (node (ref "U1") (pin "1") (pinfunction "VBAT_1") (pintype "passive+no_connect"))
    )
    (net (code "67") (name "unconnected-(U2-DIO1-Pad6)") (class "Default")
      (node (ref "U2") (pin "6") (pinfunction "DIO1_6") (pintype "passive+no_connect"))
    )
    (net (code "68") (name "unconnected-(U2-DIO2-Pad7)") (class "Default")
      (node (ref "U2") (pin "7") (pinfunction "DIO2_7") (pintype "passive+no_connect"))
    )
    (net (code "69") (name "unconnected-(U2-DIO3-Pad8)") (class "Default")
      (node (ref "U2") (pin "8") (pinfunction "DIO3_8") (pintype "passive+no_connect"))
    )
    (net (code "70") (name "unconnected-(U2-DIO4-Pad10)") (class "Default")
      (node (ref "U2") (pin "10") (pinfunction "DIO4_10") (pintype "passive+no_connect"))
    )
    (net (code "71") (name "unconnected-(U2-DIO5-Pad11)") (class "Default")
      (node (ref "U2") (pin "11") (pinfunction "DIO5_11") (pintype "passive+no_connect"))
    )
    (net (code "72") (name "unconnected-(U3-TD-Pad4)") (class "Default")
      (node (ref "U3") (pin "4") (pinfunction "TD_4") (pintype "passive+no_connect"))
    )
    (net (code "73") (name "unconnected-(U4-EP-Pad9)") (class "Default")
      (node (ref "U4") (pin "9") (pinfunction "EP_9") (pintype "passive+no_connect"))
    )
  )
)
